# hgc.net
KiCad netlist of a schematic drawn in EAGLE
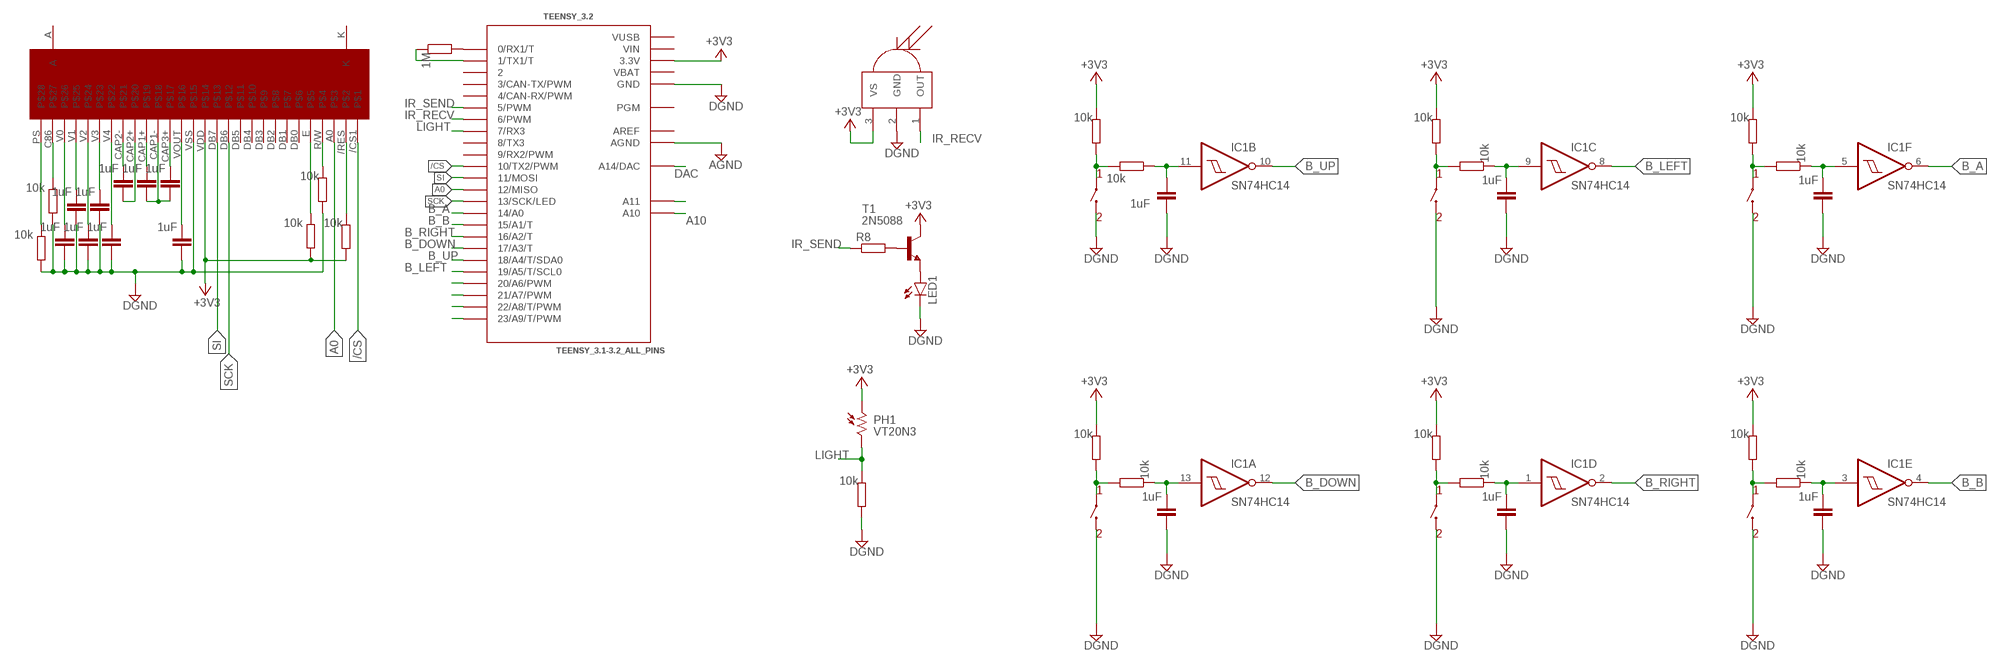
[diagram p0: schematic, sheet 1]

(export (version "E")
  (design (tool "Eeschema 10.0.6"))
  (components
    (comp (ref "A")
      (value "TACTILE_SWITCH")
      (footprint "eagle-import:SPST-NO")
      (libsource (lib "eagle-import") (part "TACTILE_SWITCH"))
    )
    (comp (ref "B")
      (value "TACTILE_SWITCH")
      (footprint "eagle-import:SPST-NO")
      (libsource (lib "eagle-import") (part "TACTILE_SWITCH"))
    )
    (comp (ref "C1")
      (value "1uF")
      (footprint "eagle-import:C0603")
      (libsource (lib "eagle-import") (part "C-EUC0603"))
    )
    (comp (ref "C2")
      (value "1uF")
      (footprint "eagle-import:C0603")
      (libsource (lib "eagle-import") (part "C-EUC0603"))
    )
    (comp (ref "C3")
      (value "1uF")
      (footprint "eagle-import:C0603")
      (libsource (lib "eagle-import") (part "C-EUC0603"))
    )
    (comp (ref "C4")
      (value "1uF")
      (footprint "eagle-import:C0603")
      (libsource (lib "eagle-import") (part "C-EUC0603"))
    )
    (comp (ref "C5")
      (value "1uF")
      (footprint "eagle-import:C0603")
      (libsource (lib "eagle-import") (part "C-EUC0603"))
    )
    (comp (ref "C6")
      (value "1uF")
      (footprint "eagle-import:C0603")
      (libsource (lib "eagle-import") (part "C-EUC0603"))
    )
    (comp (ref "C7")
      (value "1uF")
      (footprint "eagle-import:C0603")
      (libsource (lib "eagle-import") (part "C-EUC0603"))
    )
    (comp (ref "C8")
      (value "1uF")
      (footprint "eagle-import:C0603")
      (libsource (lib "eagle-import") (part "C-EUC0603"))
    )
    (comp (ref "C9")
      (value "1uF")
      (footprint "eagle-import:C0603")
      (libsource (lib "eagle-import") (part "C-EUC0603"))
    )
    (comp (ref "C10")
      (value "1uF")
      (footprint "eagle-import:C0603")
      (libsource (lib "eagle-import") (part "C-EUC0603"))
    )
    (comp (ref "C11")
      (value "1uF")
      (footprint "eagle-import:C0603")
      (libsource (lib "eagle-import") (part "C-EUC0603"))
    )
    (comp (ref "C12")
      (value "1uF")
      (footprint "eagle-import:C0603")
      (libsource (lib "eagle-import") (part "C-EUC0603"))
    )
    (comp (ref "C13")
      (value "1uF")
      (footprint "eagle-import:C0603")
      (libsource (lib "eagle-import") (part "C-EUC0603"))
    )
    (comp (ref "C14")
      (value "1uF")
      (footprint "eagle-import:C0603")
      (libsource (lib "eagle-import") (part "C-EUC0603"))
    )
    (comp (ref "C15")
      (value "1uF")
      (footprint "eagle-import:C0603")
      (libsource (lib "eagle-import") (part "C-EUC0603"))
    )
    (comp (ref "DOWN")
      (value "TACTILE_SWITCH")
      (footprint "eagle-import:SPST-NO")
      (libsource (lib "eagle-import") (part "TACTILE_SWITCH"))
    )
    (comp (ref "IC1")
      (value "SN74HC14")
      (footprint "eagle-import:SO14")
      (libsource (lib "eagle-import") (part "7414DAC"))
    )
    (comp (ref "LED1")
      (value "LED3MM")
      (footprint "eagle-import:LED3MM")
      (libsource (lib "eagle-import") (part "LED3MM"))
    )
    (comp (ref "LEFT")
      (value "TACTILE_SWITCH")
      (footprint "eagle-import:SPST-NO")
      (libsource (lib "eagle-import") (part "TACTILE_SWITCH"))
    )
    (comp (ref "PH1")
      (value "VT20N3")
      (footprint "eagle-import:TO46-VT200")
      (libsource (lib "eagle-import") (part "VT20N3"))
    )
    (comp (ref "R1")
      (value "10k")
      (footprint "eagle-import:R0603")
      (libsource (lib "eagle-import") (part "R-EU_R0603"))
    )
    (comp (ref "R2")
      (value "10k")
      (footprint "eagle-import:R0603")
      (libsource (lib "eagle-import") (part "R-EU_R0603"))
    )
    (comp (ref "R3")
      (value "10k")
      (footprint "eagle-import:R0603")
      (libsource (lib "eagle-import") (part "R-EU_R0603"))
    )
    (comp (ref "R4")
      (value "10k")
      (footprint "eagle-import:R0603")
      (libsource (lib "eagle-import") (part "R-EU_R0603"))
    )
    (comp (ref "R5")
      (value "10k")
      (footprint "eagle-import:R0603")
      (libsource (lib "eagle-import") (part "R-EU_R0603"))
    )
    (comp (ref "R6")
      (value "10k")
      (footprint "eagle-import:R0603")
      (libsource (lib "eagle-import") (part "R-EU_R0603"))
    )
    (comp (ref "R7")
      (value "10k")
      (footprint "eagle-import:R0603")
      (libsource (lib "eagle-import") (part "R-EU_R0603"))
    )
    (comp (ref "R8")
      (value "R-EU_0204/7")
      (footprint "eagle-import:0204_7")
      (libsource (lib "eagle-import") (part "R-EU_0204/7"))
    )
    (comp (ref "R9")
      (value "10k")
      (footprint "eagle-import:R0603")
      (libsource (lib "eagle-import") (part "R-EU_R0603"))
    )
    (comp (ref "R10")
      (value "10k")
      (footprint "eagle-import:R0603")
      (libsource (lib "eagle-import") (part "R-EU_R0603"))
    )
    (comp (ref "R11")
      (value "10k")
      (footprint "eagle-import:R0603")
      (libsource (lib "eagle-import") (part "R-EU_R0603"))
    )
    (comp (ref "R12")
      (value "10k")
      (footprint "eagle-import:R0603")
      (libsource (lib "eagle-import") (part "R-EU_R0603"))
    )
    (comp (ref "R13")
      (value "10k")
      (footprint "eagle-import:R0603")
      (libsource (lib "eagle-import") (part "R-EU_R0603"))
    )
    (comp (ref "R14")
      (value "1M")
      (footprint "eagle-import:R0603")
      (libsource (lib "eagle-import") (part "R-EU_R0603"))
    )
    (comp (ref "R15")
      (value "10k")
      (footprint "eagle-import:R0603")
      (libsource (lib "eagle-import") (part "R-EU_R0603"))
    )
    (comp (ref "R16")
      (value "10k")
      (footprint "eagle-import:R0603")
      (libsource (lib "eagle-import") (part "R-EU_R0603"))
    )
    (comp (ref "R18")
      (value "10k")
      (footprint "eagle-import:R0603")
      (libsource (lib "eagle-import") (part "R-EU_R0603"))
    )
    (comp (ref "R19")
      (value "10k")
      (footprint "eagle-import:R0603")
      (libsource (lib "eagle-import") (part "R-EU_R0603"))
    )
    (comp (ref "R21")
      (value "10k")
      (footprint "eagle-import:R0603")
      (libsource (lib "eagle-import") (part "R-EU_R0603"))
    )
    (comp (ref "R22")
      (value "10k")
      (footprint "eagle-import:R0603")
      (libsource (lib "eagle-import") (part "R-EU_R0603"))
    )
    (comp (ref "RIGHT")
      (value "TACTILE_SWITCH")
      (footprint "eagle-import:SPST-NO")
      (libsource (lib "eagle-import") (part "TACTILE_SWITCH"))
    )
    (comp (ref "T1")
      (value "2N5088")
      (footprint "eagle-import:TO92")
      (libsource (lib "eagle-import") (part "2N5088"))
    )
    (comp (ref "TEENSY_3.2")
      (value "TEENSY_3.1-3.2_ALL_PINS")
      (footprint "eagle-import:TEENSY_3.0-3.2&LC_ALL_PINS")
      (libsource (lib "eagle-import") (part "TEENSY_3.1-3.2_ALL_PINS"))
    )
    (comp (ref "U$2")
      (value "LCD_DISPLAY")
      (footprint "eagle-import:LCD_SCREEN")
      (libsource (lib "eagle-import") (part "LCD_DISPLAY"))
    )
    (comp (ref "U$3")
      (value "IR_RECEIVER")
      (footprint "eagle-import:T-30_V")
      (libsource (lib "eagle-import") (part "IR_RECEIVER"))
    )
    (comp (ref "UP")
      (value "TACTILE_SWITCH")
      (footprint "eagle-import:SPST-NO")
      (libsource (lib "eagle-import") (part "TACTILE_SWITCH"))
    )
  )
  (nets
    (net (code "1") (name "+3V3") (class "Default")
      (node (ref "PH1") (pin "1") (pinfunction "1_1") (pintype "passive"))
      (node (ref "R1") (pin "1") (pinfunction "1_1") (pintype "passive"))
      (node (ref "R12") (pin "1") (pinfunction "1_1") (pintype "passive"))
      (node (ref "R15") (pin "1") (pinfunction "1_1") (pintype "passive"))
      (node (ref "R18") (pin "1") (pinfunction "1_1") (pintype "passive"))
      (node (ref "R21") (pin "1") (pinfunction "1_1") (pintype "passive"))
      (node (ref "R3") (pin "2") (pinfunction "2_2") (pintype "passive"))
      (node (ref "R6") (pin "1") (pinfunction "1_1") (pintype "passive"))
      (node (ref "R9") (pin "1") (pinfunction "1_1") (pintype "passive"))
      (node (ref "T1") (pin "1") (pinfunction "C_1") (pintype "passive"))
      (node (ref "TEENSY_3.2") (pin "3.3V") (pinfunction "3.3V_3.3V") (pintype "power_in"))
      (node (ref "TEENSY_3.2") (pin "3.3V1") (pinfunction "3.3V_3.3V1") (pintype "power_in"))
      (node (ref "U$2") (pin "VDD") (pinfunction "P$14_VDD") (pintype "bidirectional"))
      (node (ref "U$3") (pin "3") (pinfunction "VS_3") (pintype "power_in"))
    )
    (net (code "2") (name "/A") (class "Default")
      (node (ref "U$2") (pin "A") (pinfunction "A_A") (pintype "power_in"))
    )
    (net (code "3") (name "/A10") (class "Default")
      (node (ref "TEENSY_3.2") (pin "A10") (pinfunction "A10_A10") (pintype "bidirectional"))
    )
    (net (code "4") (name "/AREF") (class "Default")
      (node (ref "TEENSY_3.2") (pin "AREF") (pinfunction "AREF_AREF") (pintype "power_in"))
    )
    (net (code "5") (name "/DAC") (class "Default")
      (node (ref "TEENSY_3.2") (pin "RESET/DAC") (pinfunction "A14/DAC_RESET/DAC") (pintype "bidirectional"))
    )
    (net (code "6") (name "/IR_RECV") (class "Default")
      (node (ref "TEENSY_3.2") (pin "6") (pinfunction "6/PWM_6") (pintype "bidirectional"))
      (node (ref "U$3") (pin "1") (pinfunction "OUT_1") (pintype "output"))
    )
    (net (code "7") (name "/IR_SEND") (class "Default")
      (node (ref "R8") (pin "1") (pinfunction "1_1") (pintype "passive"))
      (node (ref "TEENSY_3.2") (pin "5") (pinfunction "5/PWM_5") (pintype "bidirectional"))
    )
    (net (code "8") (name "/K") (class "Default")
      (node (ref "U$2") (pin "K") (pinfunction "K_K") (pintype "power_in"))
    )
    (net (code "9") (name "/LIGHT") (class "Default")
      (node (ref "PH1") (pin "2") (pinfunction "2_2") (pintype "passive"))
      (node (ref "R11") (pin "1") (pinfunction "1_1") (pintype "passive"))
      (node (ref "TEENSY_3.2") (pin "7") (pinfunction "7/RX3_7") (pintype "bidirectional"))
    )
    (net (code "10") (name "/VBAT") (class "Default")
      (node (ref "TEENSY_3.2") (pin "VBAT") (pinfunction "VBAT_VBAT") (pintype "power_in"))
    )
    (net (code "11") (name "/VIN") (class "Default")
      (node (ref "TEENSY_3.2") (pin "VIN") (pinfunction "VIN_VIN") (pintype "power_in"))
    )
    (net (code "12") (name "/VUSB") (class "Default")
      (node (ref "TEENSY_3.2") (pin "VUSB") (pinfunction "VUSB_VUSB") (pintype "power_in"))
    )
    (net (code "13") (name "A0") (class "Default")
      (node (ref "TEENSY_3.2") (pin "12") (pinfunction "12/MISO_12") (pintype "bidirectional"))
      (node (ref "U$2") (pin "A0") (pinfunction "P$3_A0") (pintype "bidirectional"))
    )
    (net (code "14") (name "AGND") (class "Default")
      (node (ref "TEENSY_3.2") (pin "AGND") (pinfunction "AGND_AGND") (pintype "power_in"))
    )
    (net (code "15") (name "B_A") (class "Default")
      (node (ref "IC1") (pin "6") (pinfunction "O_6") (pintype "output"))
      (node (ref "TEENSY_3.2") (pin "14/A0") (pinfunction "14/A0_14/A0") (pintype "bidirectional"))
    )
    (net (code "16") (name "B_B") (class "Default")
      (node (ref "IC1") (pin "4") (pinfunction "O_4") (pintype "output"))
      (node (ref "TEENSY_3.2") (pin "15/A1") (pinfunction "15/A1/T_15/A1") (pintype "bidirectional"))
    )
    (net (code "17") (name "B_DOWN") (class "Default")
      (node (ref "IC1") (pin "12") (pinfunction "O_12") (pintype "output"))
      (node (ref "TEENSY_3.2") (pin "17/A3") (pinfunction "17/A3/T_17/A3") (pintype "bidirectional"))
    )
    (net (code "18") (name "B_LEFT") (class "Default")
      (node (ref "IC1") (pin "8") (pinfunction "O_8") (pintype "output"))
      (node (ref "TEENSY_3.2") (pin "19/A5") (pinfunction "19/A5/T/SCL0_19/A5") (pintype "bidirectional"))
    )
    (net (code "19") (name "B_RIGHT") (class "Default")
      (node (ref "IC1") (pin "2") (pinfunction "O_2") (pintype "output"))
      (node (ref "TEENSY_3.2") (pin "16/A2") (pinfunction "16/A2/T_16/A2") (pintype "bidirectional"))
    )
    (net (code "20") (name "B_UP") (class "Default")
      (node (ref "IC1") (pin "10") (pinfunction "O_10") (pintype "output"))
      (node (ref "TEENSY_3.2") (pin "18/A4") (pinfunction "18/A4/T/SDA0_18/A4") (pintype "bidirectional"))
    )
    (net (code "21") (name "DGND") (class "Default")
      (node (ref "A") (pin "3") (pinfunction "2_3") (pintype "bidirectional"))
      (node (ref "A") (pin "4") (pinfunction "2_4") (pintype "bidirectional"))
      (node (ref "B") (pin "3") (pinfunction "2_3") (pintype "bidirectional"))
      (node (ref "B") (pin "4") (pinfunction "2_4") (pintype "bidirectional"))
      (node (ref "C1") (pin "2") (pinfunction "2_2") (pintype "passive"))
      (node (ref "C10") (pin "2") (pinfunction "2_2") (pintype "passive"))
      (node (ref "C11") (pin "2") (pinfunction "2_2") (pintype "passive"))
      (node (ref "C12") (pin "2") (pinfunction "2_2") (pintype "passive"))
      (node (ref "C13") (pin "2") (pinfunction "2_2") (pintype "passive"))
      (node (ref "C14") (pin "2") (pinfunction "2_2") (pintype "passive"))
      (node (ref "C15") (pin "2") (pinfunction "2_2") (pintype "passive"))
      (node (ref "C2") (pin "2") (pinfunction "2_2") (pintype "passive"))
      (node (ref "C3") (pin "2") (pinfunction "2_2") (pintype "passive"))
      (node (ref "C4") (pin "2") (pinfunction "2_2") (pintype "passive"))
      (node (ref "C5") (pin "2") (pinfunction "2_2") (pintype "passive"))
      (node (ref "C9") (pin "2") (pinfunction "2_2") (pintype "passive"))
      (node (ref "DOWN") (pin "3") (pinfunction "2_3") (pintype "bidirectional"))
      (node (ref "DOWN") (pin "4") (pinfunction "2_4") (pintype "bidirectional"))
      (node (ref "LED1") (pin "K") (pinfunction "C_K") (pintype "passive"))
      (node (ref "LEFT") (pin "3") (pinfunction "2_3") (pintype "bidirectional"))
      (node (ref "LEFT") (pin "4") (pinfunction "2_4") (pintype "bidirectional"))
      (node (ref "R11") (pin "2") (pinfunction "2_2") (pintype "passive"))
      (node (ref "R2") (pin "2") (pinfunction "2_2") (pintype "passive"))
      (node (ref "R4") (pin "1") (pinfunction "1_1") (pintype "passive"))
      (node (ref "R5") (pin "1") (pinfunction "1_1") (pintype "passive"))
      (node (ref "RIGHT") (pin "3") (pinfunction "2_3") (pintype "bidirectional"))
      (node (ref "RIGHT") (pin "4") (pinfunction "2_4") (pintype "bidirectional"))
      (node (ref "TEENSY_3.2") (pin "GND") (pinfunction "GND_GND") (pintype "power_in"))
      (node (ref "TEENSY_3.2") (pin "GND1") (pinfunction "GND_GND1") (pintype "power_in"))
      (node (ref "U$2") (pin "VSS") (pinfunction "P$15_VSS") (pintype "bidirectional"))
      (node (ref "U$3") (pin "2") (pinfunction "GND_2") (pintype "power_in"))
      (node (ref "UP") (pin "3") (pinfunction "2_3") (pintype "bidirectional"))
      (node (ref "UP") (pin "4") (pinfunction "2_4") (pintype "bidirectional"))
    )
    (net (code "22") (name "Net-(A-1-Pad2)") (class "Default")
      (node (ref "A") (pin "1") (pinfunction "1_1") (pintype "bidirectional"))
      (node (ref "A") (pin "2") (pinfunction "1_2") (pintype "bidirectional"))
      (node (ref "R12") (pin "2") (pinfunction "2_2") (pintype "passive"))
      (node (ref "R13") (pin "2") (pinfunction "2_2") (pintype "passive"))
    )
    (net (code "23") (name "Net-(B-1-Pad2)") (class "Default")
      (node (ref "B") (pin "1") (pinfunction "1_1") (pintype "bidirectional"))
      (node (ref "B") (pin "2") (pinfunction "1_2") (pintype "bidirectional"))
      (node (ref "R21") (pin "2") (pinfunction "2_2") (pintype "passive"))
      (node (ref "R22") (pin "2") (pinfunction "2_2") (pintype "passive"))
    )
    (net (code "24") (name "Net-(DOWN-1-Pad2)") (class "Default")
      (node (ref "DOWN") (pin "1") (pinfunction "1_1") (pintype "bidirectional"))
      (node (ref "DOWN") (pin "2") (pinfunction "1_2") (pintype "bidirectional"))
      (node (ref "R15") (pin "2") (pinfunction "2_2") (pintype "passive"))
      (node (ref "R16") (pin "2") (pinfunction "2_2") (pintype "passive"))
    )
    (net (code "25") (name "Net-(IC1A-I)") (class "Default")
      (node (ref "C13") (pin "1") (pinfunction "1_1") (pintype "passive"))
      (node (ref "IC1") (pin "13") (pinfunction "I_13") (pintype "input"))
      (node (ref "R16") (pin "1") (pinfunction "1_1") (pintype "passive"))
    )
    (net (code "26") (name "Net-(IC1B-I)") (class "Default")
      (node (ref "C10") (pin "1") (pinfunction "1_1") (pintype "passive"))
      (node (ref "IC1") (pin "11") (pinfunction "I_11") (pintype "input"))
      (node (ref "R7") (pin "1") (pinfunction "1_1") (pintype "passive"))
    )
    (net (code "27") (name "Net-(IC1C-I)") (class "Default")
      (node (ref "C11") (pin "1") (pinfunction "1_1") (pintype "passive"))
      (node (ref "IC1") (pin "9") (pinfunction "I_9") (pintype "input"))
      (node (ref "R10") (pin "1") (pinfunction "1_1") (pintype "passive"))
    )
    (net (code "28") (name "Net-(IC1D-I)") (class "Default")
      (node (ref "C14") (pin "1") (pinfunction "1_1") (pintype "passive"))
      (node (ref "IC1") (pin "1") (pinfunction "I_1") (pintype "input"))
      (node (ref "R19") (pin "1") (pinfunction "1_1") (pintype "passive"))
    )
    (net (code "29") (name "Net-(IC1E-I)") (class "Default")
      (node (ref "C15") (pin "1") (pinfunction "1_1") (pintype "passive"))
      (node (ref "IC1") (pin "3") (pinfunction "I_3") (pintype "input"))
      (node (ref "R22") (pin "1") (pinfunction "1_1") (pintype "passive"))
    )
    (net (code "30") (name "Net-(IC1F-I)") (class "Default")
      (node (ref "C12") (pin "1") (pinfunction "1_1") (pintype "passive"))
      (node (ref "IC1") (pin "5") (pinfunction "I_5") (pintype "input"))
      (node (ref "R13") (pin "1") (pinfunction "1_1") (pintype "passive"))
    )
    (net (code "31") (name "Net-(LEFT-1-Pad2)") (class "Default")
      (node (ref "LEFT") (pin "1") (pinfunction "1_1") (pintype "bidirectional"))
      (node (ref "LEFT") (pin "2") (pinfunction "1_2") (pintype "bidirectional"))
      (node (ref "R10") (pin "2") (pinfunction "2_2") (pintype "passive"))
      (node (ref "R9") (pin "2") (pinfunction "2_2") (pintype "passive"))
    )
    (net (code "32") (name "Net-(R6-Pad2)") (class "Default")
      (node (ref "R6") (pin "2") (pinfunction "2_2") (pintype "passive"))
      (node (ref "R7") (pin "2") (pinfunction "2_2") (pintype "passive"))
      (node (ref "UP") (pin "1") (pinfunction "1_1") (pintype "bidirectional"))
      (node (ref "UP") (pin "2") (pinfunction "1_2") (pintype "bidirectional"))
    )
    (net (code "33") (name "Net-(R18-Pad2)") (class "Default")
      (node (ref "R18") (pin "2") (pinfunction "2_2") (pintype "passive"))
      (node (ref "R19") (pin "2") (pinfunction "2_2") (pintype "passive"))
      (node (ref "RIGHT") (pin "1") (pinfunction "1_1") (pintype "bidirectional"))
      (node (ref "RIGHT") (pin "2") (pinfunction "1_2") (pintype "bidirectional"))
    )
    (net (code "34") (name "Net-(T1-B)") (class "Default")
      (node (ref "R8") (pin "2") (pinfunction "2_2") (pintype "passive"))
      (node (ref "T1") (pin "2") (pinfunction "B_2") (pintype "passive"))
    )
    (net (code "35") (name "Net-(T1-E)") (class "Default")
      (node (ref "LED1") (pin "A") (pinfunction "A_A") (pintype "passive"))
      (node (ref "T1") (pin "3") (pinfunction "E_3") (pintype "passive"))
    )
    (net (code "36") (name "Net-(TEENSY_3.2-0{slash}RX1{slash}T)") (class "Default")
      (node (ref "R14") (pin "2") (pinfunction "2_2") (pintype "passive"))
      (node (ref "TEENSY_3.2") (pin "0") (pinfunction "0/RX1/T_0") (pintype "bidirectional"))
    )
    (net (code "37") (name "Net-(TEENSY_3.2-1{slash}TX1{slash}T)") (class "Default")
      (node (ref "R14") (pin "1") (pinfunction "1_1") (pintype "passive"))
      (node (ref "TEENSY_3.2") (pin "1") (pinfunction "1/TX1/T_1") (pintype "bidirectional"))
    )
    (net (code "38") (name "Net-(U$2-P$2)") (class "Default")
      (node (ref "R3") (pin "1") (pinfunction "1_1") (pintype "passive"))
      (node (ref "U$2") (pin "/RES") (pinfunction "P$2_/RES") (pintype "bidirectional"))
    )
    (net (code "39") (name "Net-(U$2-P$4)") (class "Default")
      (node (ref "R2") (pin "1") (pinfunction "1_1") (pintype "passive"))
      (node (ref "U$2") (pin "R/W") (pinfunction "P$4_R/W") (pintype "bidirectional"))
    )
    (net (code "40") (name "Net-(U$2-P$5)") (class "Default")
      (node (ref "R1") (pin "2") (pinfunction "2_2") (pintype "passive"))
      (node (ref "U$2") (pin "E") (pinfunction "P$5_E") (pintype "bidirectional"))
    )
    (net (code "41") (name "Net-(U$2-P$16)") (class "Default")
      (node (ref "C9") (pin "1") (pinfunction "1_1") (pintype "passive"))
      (node (ref "U$2") (pin "VOUT") (pinfunction "P$16_VOUT") (pintype "bidirectional"))
    )
    (net (code "42") (name "Net-(U$2-P$17)") (class "Default")
      (node (ref "C8") (pin "1") (pinfunction "1_1") (pintype "passive"))
      (node (ref "U$2") (pin "CAP3+") (pinfunction "P$17_CAP3+") (pintype "bidirectional"))
    )
    (net (code "43") (name "Net-(U$2-P$18)") (class "Default")
      (node (ref "C7") (pin "2") (pinfunction "2_2") (pintype "passive"))
      (node (ref "C8") (pin "2") (pinfunction "2_2") (pintype "passive"))
      (node (ref "U$2") (pin "CAP1-") (pinfunction "P$18_CAP1-") (pintype "bidirectional"))
    )
    (net (code "44") (name "Net-(U$2-P$19)") (class "Default")
      (node (ref "C7") (pin "1") (pinfunction "1_1") (pintype "passive"))
      (node (ref "U$2") (pin "CAP1+") (pinfunction "P$19_CAP1+") (pintype "bidirectional"))
    )
    (net (code "45") (name "Net-(U$2-P$20)") (class "Default")
      (node (ref "C6") (pin "2") (pinfunction "2_2") (pintype "passive"))
      (node (ref "U$2") (pin "CAP2+") (pinfunction "P$20_CAP2+") (pintype "bidirectional"))
    )
    (net (code "46") (name "Net-(U$2-P$21)") (class "Default")
      (node (ref "C6") (pin "1") (pinfunction "1_1") (pintype "passive"))
      (node (ref "U$2") (pin "CAP2-") (pinfunction "P$21_CAP2-") (pintype "bidirectional"))
    )
    (net (code "47") (name "Net-(U$2-P$22)") (class "Default")
      (node (ref "C5") (pin "1") (pinfunction "1_1") (pintype "passive"))
      (node (ref "U$2") (pin "V4") (pinfunction "P$22_V4") (pintype "bidirectional"))
    )
    (net (code "48") (name "Net-(U$2-P$23)") (class "Default")
      (node (ref "C4") (pin "1") (pinfunction "1_1") (pintype "passive"))
      (node (ref "U$2") (pin "V3") (pinfunction "P$23_V3") (pintype "bidirectional"))
    )
    (net (code "49") (name "Net-(U$2-P$24)") (class "Default")
      (node (ref "C3") (pin "1") (pinfunction "1_1") (pintype "passive"))
      (node (ref "U$2") (pin "V2") (pinfunction "P$24_V2") (pintype "bidirectional"))
    )
    (net (code "50") (name "Net-(U$2-P$25)") (class "Default")
      (node (ref "C2") (pin "1") (pinfunction "1_1") (pintype "passive"))
      (node (ref "U$2") (pin "V1") (pinfunction "P$25_V1") (pintype "bidirectional"))
    )
    (net (code "51") (name "Net-(U$2-P$26)") (class "Default")
      (node (ref "C1") (pin "1") (pinfunction "1_1") (pintype "passive"))
      (node (ref "U$2") (pin "V0") (pinfunction "P$26_V0") (pintype "bidirectional"))
    )
    (net (code "52") (name "Net-(U$2-P$27)") (class "Default")
      (node (ref "R5") (pin "2") (pinfunction "2_2") (pintype "passive"))
      (node (ref "U$2") (pin "C86") (pinfunction "P$27_C86") (pintype "bidirectional"))
    )
    (net (code "53") (name "Net-(U$2-P$28)") (class "Default")
      (node (ref "R4") (pin "2") (pinfunction "2_2") (pintype "passive"))
      (node (ref "U$2") (pin "PS") (pinfunction "P$28_PS") (pintype "bidirectional"))
    )
    (net (code "54") (name "SCK") (class "Default")
      (node (ref "TEENSY_3.2") (pin "13") (pinfunction "13/SCK/LED_13") (pintype "bidirectional"))
      (node (ref "U$2") (pin "DB6") (pinfunction "P$12_DB6") (pintype "bidirectional"))
    )
    (net (code "55") (name "SI") (class "Default")
      (node (ref "TEENSY_3.2") (pin "11") (pinfunction "11/MOSI_11") (pintype "bidirectional"))
      (node (ref "U$2") (pin "DB7") (pinfunction "P$13_DB7") (pintype "bidirectional"))
    )
    (net (code "56") (name "unconnected-(TEENSY_3.2-3{slash}CAN-TX{slash}PWM-Pad3)") (class "Default")
      (node (ref "TEENSY_3.2") (pin "3") (pinfunction "3/CAN-TX/PWM_3") (pintype "bidirectional"))
    )
    (net (code "57") (name "unconnected-(TEENSY_3.2-4{slash}CAN-RX{slash}PWM-Pad4)") (class "Default")
      (node (ref "TEENSY_3.2") (pin "4") (pinfunction "4/CAN-RX/PWM_4") (pintype "bidirectional"))
    )
    (net (code "58") (name "unconnected-(TEENSY_3.2-8{slash}TX3-Pad8)") (class "Default")
      (node (ref "TEENSY_3.2") (pin "8") (pinfunction "8/TX3_8") (pintype "bidirectional"))
    )
    (net (code "59") (name "unconnected-(TEENSY_3.2-9{slash}RX2{slash}PWM-Pad9)") (class "Default")
      (node (ref "TEENSY_3.2") (pin "9") (pinfunction "9/RX2/PWM_9") (pintype "bidirectional"))
    )
    (net (code "60") (name "unconnected-(TEENSY_3.2-20{slash}A6{slash}PWM-Pad20{slash}A6)") (class "Default")
      (node (ref "TEENSY_3.2") (pin "20/A6") (pinfunction "20/A6/PWM_20/A6") (pintype "bidirectional"))
    )
    (net (code "61") (name "unconnected-(TEENSY_3.2-21{slash}A7{slash}PWM-Pad21{slash}A7)") (class "Default")
      (node (ref "TEENSY_3.2") (pin "21/A7") (pinfunction "21/A7/PWM_21/A7") (pintype "bidirectional"))
    )
    (net (code "62") (name "unconnected-(TEENSY_3.2-22{slash}A8{slash}T{slash}PWM-Pad22{slash}A8)") (class "Default")
      (node (ref "TEENSY_3.2") (pin "22/A8") (pinfunction "22/A8/T/PWM_22/A8") (pintype "bidirectional"))
    )
    (net (code "63") (name "unconnected-(TEENSY_3.2-23{slash}A9{slash}T{slash}PWM-Pad23{slash}A9)") (class "Default")
      (node (ref "TEENSY_3.2") (pin "23/A9") (pinfunction "23/A9/T/PWM_23/A9") (pintype "bidirectional"))
    )
    (net (code "64") (name "unconnected-(TEENSY_3.2-Pad2)") (class "Default")
      (node (ref "TEENSY_3.2") (pin "2") (pinfunction "2_2") (pintype "bidirectional"))
    )
    (net (code "65") (name "unconnected-(TEENSY_3.2-PadA11)") (class "Default")
      (node (ref "TEENSY_3.2") (pin "A11") (pinfunction "A11_A11") (pintype "bidirectional"))
    )
    (net (code "66") (name "unconnected-(TEENSY_3.2-PadPGM)") (class "Default")
      (node (ref "TEENSY_3.2") (pin "PGM") (pinfunction "PGM_PGM") (pintype "bidirectional"))
    )
    (net (code "67") (name "unconnected-(U$2-P$6-PadDB0)") (class "Default")
      (node (ref "U$2") (pin "DB0") (pinfunction "P$6_DB0") (pintype "bidirectional"))
    )
    (net (code "68") (name "unconnected-(U$2-P$7-PadDB1)") (class "Default")
      (node (ref "U$2") (pin "DB1") (pinfunction "P$7_DB1") (pintype "bidirectional"))
    )
    (net (code "69") (name "unconnected-(U$2-P$8-PadDB2)") (class "Default")
      (node (ref "U$2") (pin "DB2") (pinfunction "P$8_DB2") (pintype "bidirectional"))
    )
    (net (code "70") (name "unconnected-(U$2-P$9-PadDB3)") (class "Default")
      (node (ref "U$2") (pin "DB3") (pinfunction "P$9_DB3") (pintype "bidirectional"))
    )
    (net (code "71") (name "unconnected-(U$2-P$10-PadDB4)") (class "Default")
      (node (ref "U$2") (pin "DB4") (pinfunction "P$10_DB4") (pintype "bidirectional"))
    )
    (net (code "72") (name "unconnected-(U$2-P$11-PadDB5)") (class "Default")
      (node (ref "U$2") (pin "DB5") (pinfunction "P$11_DB5") (pintype "bidirectional"))
    )
    (net (code "73") (name "{slash}CS") (class "Default")
      (node (ref "TEENSY_3.2") (pin "10") (pinfunction "10/TX2/PWM_10") (pintype "bidirectional"))
      (node (ref "U$2") (pin "/CS1") (pinfunction "P$1_/CS1") (pintype "bidirectional"))
    )
  )
)
